# NFC.net
KiCad netlist of a schematic drawn in Altium Designer
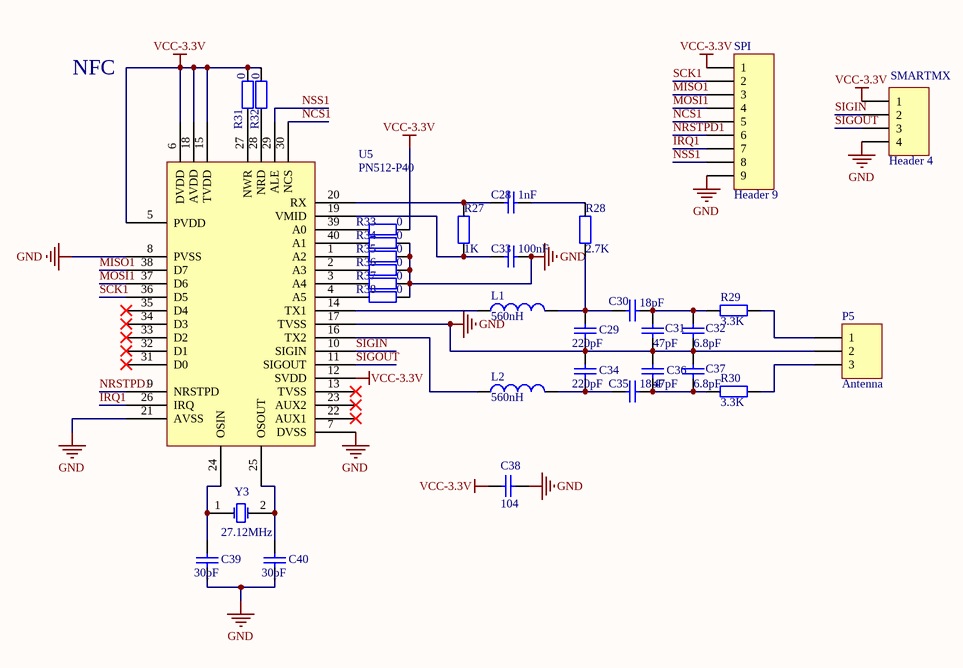
[diagram p0: NFC.SchDoc]

(export (version "E")
  (design (tool "Eeschema 10.0.6"))
  (components
    (comp (ref "C28")
      (value "1nF")
      (footprint "1608[0603]")
      (description "Capacitor")
      (fields (field (name "Comment") "Cap") (field (name "PUBLISHER") "Altium Limited"))
      (libsource (lib "common") (part "Cap"))
    )
    (comp (ref "C29")
      (value "220pF")
      (footprint "1608[0603]")
      (description "Capacitor")
      (fields (field (name "Comment") "Cap") (field (name "PUBLISHER") "Altium Limited"))
      (libsource (lib "common") (part "Cap"))
    )
    (comp (ref "C30")
      (value "18pF")
      (footprint "1608[0603]")
      (description "Capacitor")
      (fields (field (name "Comment") "Cap") (field (name "PUBLISHER") "Altium Limited"))
      (libsource (lib "common") (part "Cap"))
    )
    (comp (ref "C31")
      (value "47pF")
      (footprint "1608[0603]")
      (description "Capacitor")
      (fields (field (name "Comment") "Cap") (field (name "PUBLISHER") "Altium Limited"))
      (libsource (lib "common") (part "Cap"))
    )
    (comp (ref "C32")
      (value "6.8pF")
      (footprint "1608[0603]")
      (description "Capacitor")
      (fields (field (name "Comment") "Cap") (field (name "PUBLISHER") "Altium Limited"))
      (libsource (lib "common") (part "Cap"))
    )
    (comp (ref "C33")
      (value "100nF")
      (footprint "1608[0603]")
      (description "Capacitor")
      (fields (field (name "Comment") "Cap") (field (name "PUBLISHER") "Altium Limited"))
      (libsource (lib "common") (part "Cap"))
    )
    (comp (ref "C34")
      (value "220pF")
      (footprint "1608[0603]")
      (description "Capacitor")
      (fields (field (name "Comment") "Cap") (field (name "PUBLISHER") "Altium Limited"))
      (libsource (lib "common") (part "Cap"))
    )
    (comp (ref "C35")
      (value "18pF")
      (footprint "1608[0603]")
      (description "Capacitor")
      (fields (field (name "Comment") "Cap") (field (name "PUBLISHER") "Altium Limited"))
      (libsource (lib "common") (part "Cap"))
    )
    (comp (ref "C36")
      (value "47pF")
      (footprint "1608[0603]")
      (description "Capacitor")
      (fields (field (name "Comment") "Cap") (field (name "PUBLISHER") "Altium Limited"))
      (libsource (lib "common") (part "Cap"))
    )
    (comp (ref "C37")
      (value "6.8pF")
      (footprint "1608[0603]")
      (description "Capacitor")
      (fields (field (name "Comment") "Cap") (field (name "PUBLISHER") "Altium Limited"))
      (libsource (lib "common") (part "Cap"))
    )
    (comp (ref "C38")
      (value "104")
      (footprint "1608[0603]")
      (description "Capacitor")
      (fields (field (name "Comment") "Cap") (field (name "PUBLISHER") "Altium Limited"))
      (libsource (lib "common") (part "Cap"))
    )
    (comp (ref "C39")
      (value "30pF")
      (footprint "1608[0603]")
      (description "Capacitor")
      (fields (field (name "Comment") "Cap") (field (name "PUBLISHER") "Altium Limited"))
      (libsource (lib "common") (part "Cap"))
    )
    (comp (ref "C40")
      (value "30pF")
      (footprint "1608[0603]")
      (description "Capacitor")
      (fields (field (name "Comment") "Cap") (field (name "PUBLISHER") "Altium Limited"))
      (libsource (lib "common") (part "Cap"))
    )
    (comp (ref "L1")
      (value "560nH")
      (footprint "0402-A")
      (description "Inductor")
      (fields (field (name "PUBLISHER") "Altium Limited"))
      (libsource (lib "Miscellaneous Devices") (part "Inductor"))
    )
    (comp (ref "L2")
      (value "560nH")
      (footprint "0402-A")
      (description "Inductor")
      (fields (field (name "PUBLISHER") "Altium Limited"))
      (libsource (lib "Miscellaneous Devices") (part "Inductor"))
    )
    (comp (ref "P5")
      (value "Antenna")
      (footprint "HDR1X3")
      (description "Header, 3-Pin")
      (fields (field (name "PUBLISHER") "Altium Limited"))
      (libsource (lib "Miscellaneous Connectors") (part "Header 3"))
    )
    (comp (ref "R27")
      (value "1K")
      (footprint "1608[0603]")
      (description "Resistor")
      (fields (field (name "Comment") "RES") (field (name "PUBLISHER") "Altium Limited"))
      (libsource (lib "") (part "RES_1"))
    )
    (comp (ref "R28")
      (value "2.7K")
      (footprint "1608[0603]")
      (description "Resistor")
      (fields (field (name "Comment") "RES") (field (name "PUBLISHER") "Altium Limited"))
      (libsource (lib "") (part "RES_1"))
    )
    (comp (ref "R29")
      (value "3.3K")
      (footprint "1608[0603]")
      (description "Resistor")
      (fields (field (name "Comment") "RES") (field (name "PUBLISHER") "Altium Limited"))
      (libsource (lib "common") (part "RES"))
    )
    (comp (ref "R30")
      (value "3.3K")
      (footprint "1608[0603]")
      (description "Resistor")
      (fields (field (name "Comment") "RES") (field (name "PUBLISHER") "Altium Limited"))
      (libsource (lib "common") (part "RES"))
    )
    (comp (ref "R31")
      (value "0")
      (footprint "1608[0603]")
      (description "Resistor")
      (fields (field (name "Comment") "RES") (field (name "PUBLISHER") "Altium Limited"))
      (libsource (lib "") (part "RES_1"))
    )
    (comp (ref "R32")
      (value "0")
      (footprint "1608[0603]")
      (description "Resistor")
      (fields (field (name "Comment") "RES") (field (name "PUBLISHER") "Altium Limited"))
      (libsource (lib "") (part "RES_1"))
    )
    (comp (ref "R33")
      (value "0")
      (footprint "1608[0603]")
      (description "Resistor")
      (fields (field (name "Comment") "RES") (field (name "PUBLISHER") "Altium Limited"))
      (libsource (lib "common") (part "RES"))
    )
    (comp (ref "R34")
      (value "0")
      (footprint "1608[0603]")
      (description "Resistor")
      (fields (field (name "Comment") "RES") (field (name "PUBLISHER") "Altium Limited"))
      (libsource (lib "common") (part "RES"))
    )
    (comp (ref "R35")
      (value "0")
      (footprint "1608[0603]")
      (description "Resistor")
      (fields (field (name "Comment") "RES") (field (name "PUBLISHER") "Altium Limited"))
      (libsource (lib "common") (part "RES"))
    )
    (comp (ref "R36")
      (value "0")
      (footprint "1608[0603]")
      (description "Resistor")
      (fields (field (name "Comment") "RES") (field (name "PUBLISHER") "Altium Limited"))
      (libsource (lib "common") (part "RES"))
    )
    (comp (ref "R37")
      (value "0")
      (footprint "1608[0603]")
      (description "Resistor")
      (fields (field (name "Comment") "RES") (field (name "PUBLISHER") "Altium Limited"))
      (libsource (lib "common") (part "RES"))
    )
    (comp (ref "R38")
      (value "0")
      (footprint "1608[0603]")
      (description "Resistor")
      (fields (field (name "Comment") "RES") (field (name "PUBLISHER") "Altium Limited"))
      (libsource (lib "common") (part "RES"))
    )
    (comp (ref "SMARTMX")
      (value "Header 4")
      (footprint "HDR1X4")
      (description "Header, 4-Pin")
      (fields (field (name "PUBLISHER") "Altium Limited"))
      (libsource (lib "Miscellaneous Connectors") (part "Header 4"))
    )
    (comp (ref "SPI")
      (value "Header 9")
      (footprint "HDR1X9")
      (description "Header, 9-Pin")
      (fields (field (name "PUBLISHER") "Altium Limited"))
      (libsource (lib "Miscellaneous Connectors") (part "Header 9"))
    )
    (comp (ref "U5")
      (value "PN512-P40")
      (footprint "QFN50P600X600-40VN")
      (libsource (lib "*") (part "PN511-P40"))
    )
    (comp (ref "Y3")
      (value "27.12MHz")
      (footprint "XTAL")
      (description "Crystal Oscillator")
      (fields (field (name "PUBLISHER") "Altium Limited"))
      (libsource (lib "common") (part "XTAL"))
    )
  )
  (nets
    (net (code "1") (name "/IRQ1") (class "Default")
      (node (ref "SPI") (pin "7") (pinfunction "7_7") (pintype "passive"))
      (node (ref "U5") (pin "26") (pinfunction "IRQ_26") (pintype "passive"))
    )
    (net (code "2") (name "/MISO1") (class "Default")
      (node (ref "SPI") (pin "3") (pinfunction "3_3") (pintype "passive"))
      (node (ref "U5") (pin "38") (pinfunction "D7_38") (pintype "passive"))
    )
    (net (code "3") (name "/MOSI1") (class "Default")
      (node (ref "SPI") (pin "4") (pinfunction "4_4") (pintype "passive"))
      (node (ref "U5") (pin "37") (pinfunction "D6_37") (pintype "passive"))
    )
    (net (code "4") (name "/NCS1") (class "Default")
      (node (ref "SPI") (pin "5") (pinfunction "5_5") (pintype "passive"))
      (node (ref "U5") (pin "30") (pinfunction "NCS_30") (pintype "passive"))
    )
    (net (code "5") (name "/NRSTPD1") (class "Default")
      (node (ref "SPI") (pin "6") (pinfunction "6_6") (pintype "passive"))
      (node (ref "U5") (pin "9") (pinfunction "NRSTPD_9") (pintype "passive"))
    )
    (net (code "6") (name "/NSS1") (class "Default")
      (node (ref "SPI") (pin "8") (pinfunction "8_8") (pintype "passive"))
      (node (ref "U5") (pin "29") (pinfunction "ALE_29") (pintype "passive"))
    )
    (net (code "7") (name "/SCK1") (class "Default")
      (node (ref "SPI") (pin "2") (pinfunction "2_2") (pintype "passive"))
      (node (ref "U5") (pin "36") (pinfunction "D5_36") (pintype "passive"))
    )
    (net (code "8") (name "/SIGIN") (class "Default")
      (node (ref "SMARTMX") (pin "2") (pinfunction "2_2") (pintype "passive"))
      (node (ref "U5") (pin "10") (pinfunction "SIGIN_10") (pintype "passive"))
    )
    (net (code "9") (name "/SIGOUT") (class "Default")
      (node (ref "SMARTMX") (pin "3") (pinfunction "3_3") (pintype "passive"))
      (node (ref "U5") (pin "11") (pinfunction "SIGOUT_11") (pintype "passive"))
    )
    (net (code "10") (name "GND") (class "Default")
      (node (ref "C29") (pin "1") (pinfunction "1_1") (pintype "passive"))
      (node (ref "C31") (pin "1") (pinfunction "1_1") (pintype "passive"))
      (node (ref "C32") (pin "1") (pinfunction "1_1") (pintype "passive"))
      (node (ref "C33") (pin "2") (pinfunction "2_2") (pintype "passive"))
      (node (ref "C34") (pin "2") (pinfunction "2_2") (pintype "passive"))
      (node (ref "C36") (pin "2") (pinfunction "2_2") (pintype "passive"))
      (node (ref "C37") (pin "2") (pinfunction "2_2") (pintype "passive"))
      (node (ref "C38") (pin "1") (pinfunction "1_1") (pintype "passive"))
      (node (ref "C39") (pin "1") (pinfunction "1_1") (pintype "passive"))
      (node (ref "C40") (pin "1") (pinfunction "1_1") (pintype "passive"))
      (node (ref "P5") (pin "2") (pinfunction "2_2") (pintype "passive"))
      (node (ref "R34") (pin "1") (pinfunction "1_1") (pintype "passive"))
      (node (ref "R35") (pin "1") (pinfunction "1_1") (pintype "passive"))
      (node (ref "R36") (pin "1") (pinfunction "1_1") (pintype "passive"))
      (node (ref "R37") (pin "1") (pinfunction "1_1") (pintype "passive"))
      (node (ref "R38") (pin "1") (pinfunction "1_1") (pintype "passive"))
      (node (ref "SMARTMX") (pin "4") (pinfunction "4_4") (pintype "passive"))
      (node (ref "SPI") (pin "9") (pinfunction "9_9") (pintype "passive"))
      (node (ref "U5") (pin "17") (pinfunction "TVSS_17") (pintype "passive"))
      (node (ref "U5") (pin "21") (pinfunction "AVSS_21") (pintype "passive"))
      (node (ref "U5") (pin "7") (pinfunction "DVSS_7") (pintype "passive"))
      (node (ref "U5") (pin "8") (pinfunction "PVSS_8") (pintype "passive"))
    )
    (net (code "11") (name "Net-(C28-Pad2)") (class "Default")
      (node (ref "C28") (pin "2") (pinfunction "2_2") (pintype "passive"))
      (node (ref "R28") (pin "2") (pinfunction "2_2") (pintype "passive"))
    )
    (net (code "12") (name "Net-(C29-Pad2)") (class "Default")
      (node (ref "C29") (pin "2") (pinfunction "2_2") (pintype "passive"))
      (node (ref "C30") (pin "1") (pinfunction "1_1") (pintype "passive"))
      (node (ref "L1") (pin "2") (pinfunction "2_2") (pintype "passive"))
      (node (ref "R28") (pin "1") (pinfunction "1_1") (pintype "passive"))
    )
    (net (code "13") (name "Net-(C30-Pad2)") (class "Default")
      (node (ref "C30") (pin "2") (pinfunction "2_2") (pintype "passive"))
      (node (ref "C31") (pin "2") (pinfunction "2_2") (pintype "passive"))
      (node (ref "C32") (pin "2") (pinfunction "2_2") (pintype "passive"))
      (node (ref "R29") (pin "2") (pinfunction "2_2") (pintype "passive"))
    )
    (net (code "14") (name "Net-(C34-Pad1)") (class "Default")
      (node (ref "C34") (pin "1") (pinfunction "1_1") (pintype "passive"))
      (node (ref "C35") (pin "1") (pinfunction "1_1") (pintype "passive"))
      (node (ref "L2") (pin "2") (pinfunction "2_2") (pintype "passive"))
    )
    (net (code "15") (name "Net-(C35-Pad2)") (class "Default")
      (node (ref "C35") (pin "2") (pinfunction "2_2") (pintype "passive"))
      (node (ref "C36") (pin "1") (pinfunction "1_1") (pintype "passive"))
      (node (ref "C37") (pin "1") (pinfunction "1_1") (pintype "passive"))
      (node (ref "R30") (pin "2") (pinfunction "2_2") (pintype "passive"))
    )
    (net (code "16") (name "Net-(P5-Pad1)") (class "Default")
      (node (ref "P5") (pin "1") (pinfunction "1_1") (pintype "passive"))
      (node (ref "R29") (pin "1") (pinfunction "1_1") (pintype "passive"))
    )
    (net (code "17") (name "Net-(P5-Pad3)") (class "Default")
      (node (ref "P5") (pin "3") (pinfunction "3_3") (pintype "passive"))
      (node (ref "R30") (pin "1") (pinfunction "1_1") (pintype "passive"))
    )
    (net (code "18") (name "Net-(U5-A0)") (class "Default")
      (node (ref "R33") (pin "2") (pinfunction "2_2") (pintype "passive"))
      (node (ref "U5") (pin "39") (pinfunction "A0_39") (pintype "passive"))
    )
    (net (code "19") (name "Net-(U5-A1)") (class "Default")
      (node (ref "R34") (pin "2") (pinfunction "2_2") (pintype "passive"))
      (node (ref "U5") (pin "40") (pinfunction "A1_40") (pintype "passive"))
    )
    (net (code "20") (name "Net-(U5-A2)") (class "Default")
      (node (ref "R35") (pin "2") (pinfunction "2_2") (pintype "passive"))
      (node (ref "U5") (pin "1") (pinfunction "A2_1") (pintype "passive"))
    )
    (net (code "21") (name "Net-(U5-A3)") (class "Default")
      (node (ref "R36") (pin "2") (pinfunction "2_2") (pintype "passive"))
      (node (ref "U5") (pin "2") (pinfunction "A3_2") (pintype "passive"))
    )
    (net (code "22") (name "Net-(U5-A4)") (class "Default")
      (node (ref "R37") (pin "2") (pinfunction "2_2") (pintype "passive"))
      (node (ref "U5") (pin "3") (pinfunction "A4_3") (pintype "passive"))
    )
    (net (code "23") (name "Net-(U5-A5)") (class "Default")
      (node (ref "R38") (pin "2") (pinfunction "2_2") (pintype "passive"))
      (node (ref "U5") (pin "4") (pinfunction "A5_4") (pintype "passive"))
    )
    (net (code "24") (name "Net-(U5-NRD)") (class "Default")
      (node (ref "R32") (pin "1") (pinfunction "1_1") (pintype "passive"))
      (node (ref "U5") (pin "28") (pinfunction "NRD_28") (pintype "passive"))
    )
    (net (code "25") (name "Net-(U5-NWR)") (class "Default")
      (node (ref "R31") (pin "1") (pinfunction "1_1") (pintype "passive"))
      (node (ref "U5") (pin "27") (pinfunction "NWR_27") (pintype "passive"))
    )
    (net (code "26") (name "Net-(U5-OSIN)") (class "Default")
      (node (ref "C39") (pin "2") (pinfunction "2_2") (pintype "passive"))
      (node (ref "U5") (pin "24") (pinfunction "OSIN_24") (pintype "passive"))
      (node (ref "Y3") (pin "1") (pinfunction "OSC1_1") (pintype "passive"))
    )
    (net (code "27") (name "Net-(U5-OSOUT)") (class "Default")
      (node (ref "C40") (pin "2") (pinfunction "2_2") (pintype "passive"))
      (node (ref "U5") (pin "25") (pinfunction "OSOUT_25") (pintype "passive"))
      (node (ref "Y3") (pin "2") (pinfunction "OSC2_2") (pintype "passive"))
    )
    (net (code "28") (name "Net-(U5-RX)") (class "Default")
      (node (ref "C28") (pin "1") (pinfunction "1_1") (pintype "passive"))
      (node (ref "R27") (pin "2") (pinfunction "2_2") (pintype "passive"))
      (node (ref "U5") (pin "20") (pinfunction "RX_20") (pintype "passive"))
    )
    (net (code "29") (name "Net-(U5-TX1)") (class "Default")
      (node (ref "L1") (pin "1") (pinfunction "1_1") (pintype "passive"))
      (node (ref "U5") (pin "14") (pinfunction "TX1_14") (pintype "passive"))
    )
    (net (code "30") (name "Net-(U5-TX2)") (class "Default")
      (node (ref "L2") (pin "1") (pinfunction "1_1") (pintype "passive"))
      (node (ref "U5") (pin "16") (pinfunction "TX2_16") (pintype "passive"))
    )
    (net (code "31") (name "Net-(U5-VMID)") (class "Default")
      (node (ref "C33") (pin "1") (pinfunction "1_1") (pintype "passive"))
      (node (ref "R27") (pin "1") (pinfunction "1_1") (pintype "passive"))
      (node (ref "U5") (pin "19") (pinfunction "VMID_19") (pintype "passive"))
    )
    (net (code "32") (name "VCC-3.3V") (class "Default")
      (node (ref "C38") (pin "2") (pinfunction "2_2") (pintype "passive"))
      (node (ref "R31") (pin "2") (pinfunction "2_2") (pintype "passive"))
      (node (ref "R32") (pin "2") (pinfunction "2_2") (pintype "passive"))
      (node (ref "R33") (pin "1") (pinfunction "1_1") (pintype "passive"))
      (node (ref "SMARTMX") (pin "1") (pinfunction "1_1") (pintype "passive"))
      (node (ref "SPI") (pin "1") (pinfunction "1_1") (pintype "passive"))
      (node (ref "U5") (pin "12") (pinfunction "SVDD_12") (pintype "passive"))
      (node (ref "U5") (pin "15") (pinfunction "TVDD_15") (pintype "passive"))
      (node (ref "U5") (pin "18") (pinfunction "AVDD_18") (pintype "passive"))
      (node (ref "U5") (pin "5") (pinfunction "PVDD_5") (pintype "passive"))
      (node (ref "U5") (pin "6") (pinfunction "DVDD_6") (pintype "passive"))
    )
    (net (code "33") (name "unconnected-(U5-AUX1-Pad22)") (class "Default")
      (node (ref "U5") (pin "22") (pinfunction "AUX1_22") (pintype "passive+no_connect"))
    )
    (net (code "34") (name "unconnected-(U5-AUX2-Pad23)") (class "Default")
      (node (ref "U5") (pin "23") (pinfunction "AUX2_23") (pintype "passive+no_connect"))
    )
    (net (code "35") (name "unconnected-(U5-D0-Pad31)") (class "Default")
      (node (ref "U5") (pin "31") (pinfunction "D0_31") (pintype "passive+no_connect"))
    )
    (net (code "36") (name "unconnected-(U5-D1-Pad32)") (class "Default")
      (node (ref "U5") (pin "32") (pinfunction "D1_32") (pintype "passive+no_connect"))
    )
    (net (code "37") (name "unconnected-(U5-D2-Pad33)") (class "Default")
      (node (ref "U5") (pin "33") (pinfunction "D2_33") (pintype "passive+no_connect"))
    )
    (net (code "38") (name "unconnected-(U5-D3-Pad34)") (class "Default")
      (node (ref "U5") (pin "34") (pinfunction "D3_34") (pintype "passive+no_connect"))
    )
    (net (code "39") (name "unconnected-(U5-D4-Pad35)") (class "Default")
      (node (ref "U5") (pin "35") (pinfunction "D4_35") (pintype "passive+no_connect"))
    )
    (net (code "40") (name "unconnected-(U5-TVSS-Pad13)") (class "Default")
      (node (ref "U5") (pin "13") (pinfunction "TVSS_13") (pintype "passive+no_connect"))
    )
  )
)
